# simple-loop-active1.net
KiCad netlist of a schematic drawn in EAGLE
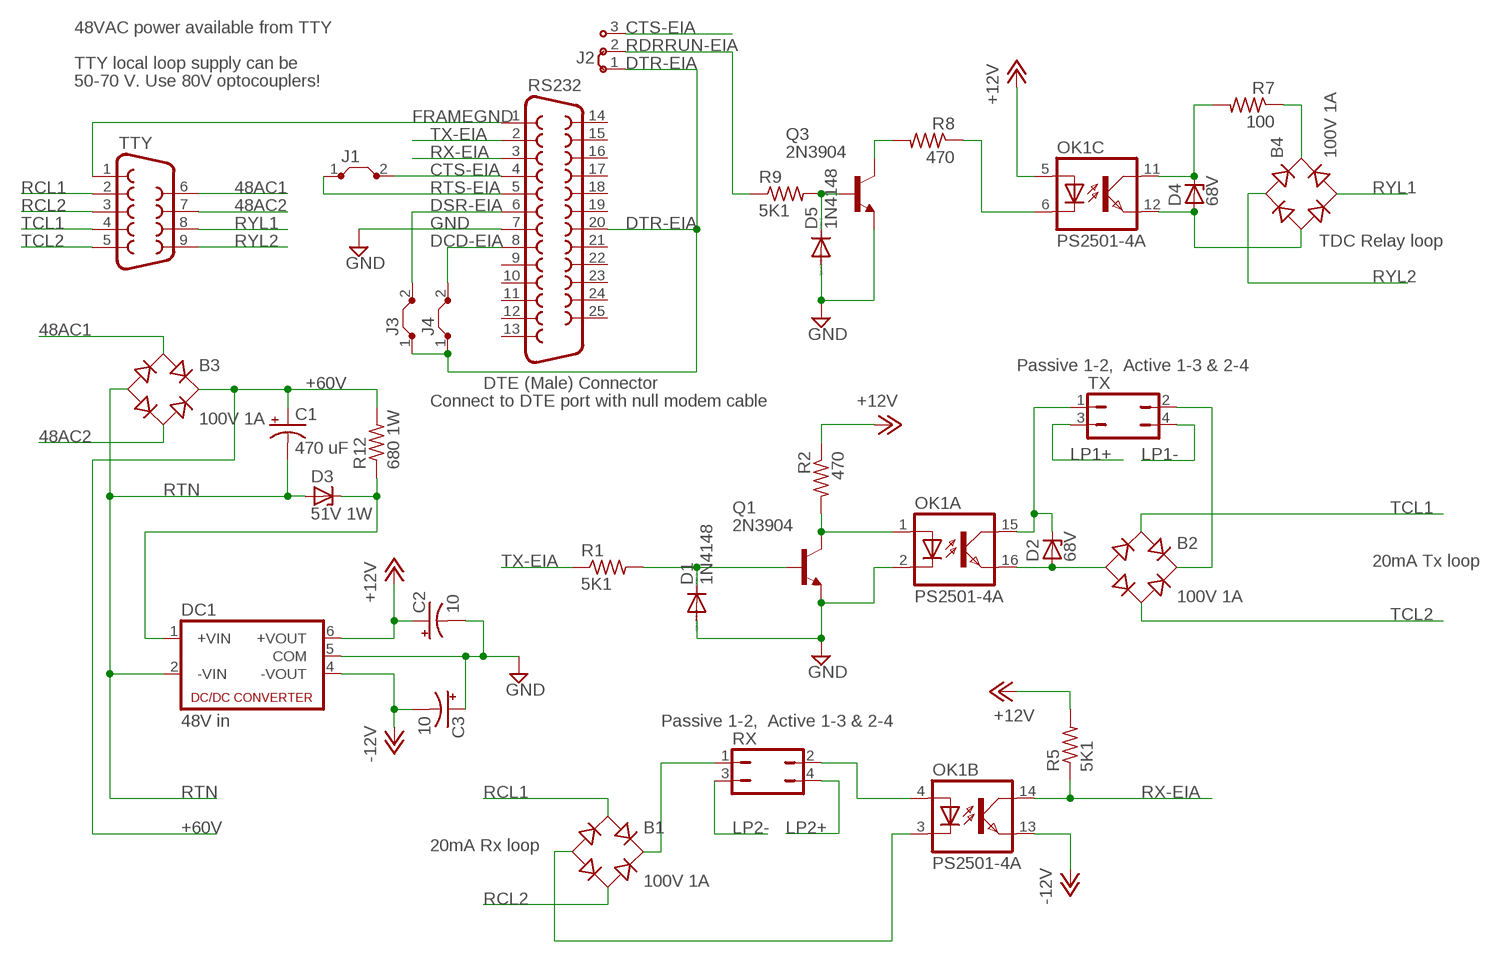
[diagram p0: schematic, sheet 1]
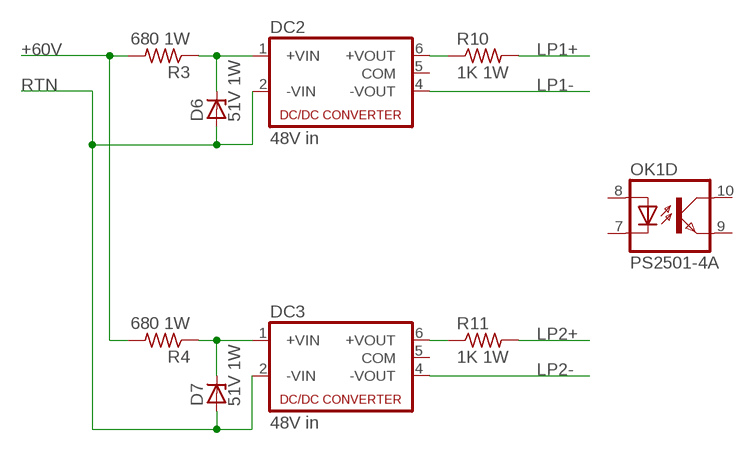
[diagram p1: schematic, sheet 2]

(export (version "E")
  (design (tool "Eeschema 10.0.6"))
  (components
    (comp (ref "B1")
      (value "100V 1A")
      (footprint "eagle-import:RB1A")
      (libsource (lib "eagle-import") (part "RB1A"))
    )
    (comp (ref "B2")
      (value "100V 1A")
      (footprint "eagle-import:RB1A")
      (libsource (lib "eagle-import") (part "RB1A"))
    )
    (comp (ref "B3")
      (value "100V 1A")
      (footprint "eagle-import:RB1A")
      (libsource (lib "eagle-import") (part "RB1A"))
    )
    (comp (ref "B4")
      (value "100V 1A")
      (footprint "eagle-import:RB1A")
      (libsource (lib "eagle-import") (part "RB1A"))
    )
    (comp (ref "C1")
      (value "470 uF")
      (footprint "eagle-import:E7,5-18")
      (libsource (lib "eagle-import") (part "CPOL-USE7.5-18"))
    )
    (comp (ref "C2")
      (value "10")
      (footprint "eagle-import:B45181A")
      (libsource (lib "eagle-import") (part "CPOL-USB45181A"))
    )
    (comp (ref "C3")
      (value "10")
      (footprint "eagle-import:B45181A")
      (libsource (lib "eagle-import") (part "CPOL-USB45181A"))
    )
    (comp (ref "D1")
      (value "1N4148")
      (footprint "eagle-import:DO35-10")
      (libsource (lib "eagle-import") (part "1N4148DO35-10"))
    )
    (comp (ref "D2")
      (value "68V")
      (footprint "eagle-import:DO41Z10")
      (libsource (lib "eagle-import") (part "ZENER-DIODEDO41Z10"))
    )
    (comp (ref "D3")
      (value "51V 1W")
      (footprint "eagle-import:DO41Z10")
      (libsource (lib "eagle-import") (part "ZENER-DIODEDO41Z10"))
    )
    (comp (ref "D4")
      (value "68V")
      (footprint "eagle-import:DO41Z10")
      (libsource (lib "eagle-import") (part "ZENER-DIODEDO41Z10"))
    )
    (comp (ref "D5")
      (value "1N4148")
      (footprint "eagle-import:DO35-10")
      (libsource (lib "eagle-import") (part "1N4148DO35-10"))
    )
    (comp (ref "DC1")
      (value "48V in")
      (footprint "eagle-import:NMA")
      (fields (field (name "MF") "C & D TECHNOLOGIES, INC") (field (name "MPN") "NMA0515SC"))
      (libsource (lib "eagle-import") (part "NMA"))
    )
    (comp (ref "J1")
      (value "J5MM")
      (footprint "eagle-import:05")
      (libsource (lib "eagle-import") (part "J5MM"))
    )
    (comp (ref "J2")
      (value "J2X5MM")
      (footprint "eagle-import:05C")
      (libsource (lib "eagle-import") (part "J2X5MM"))
    )
    (comp (ref "J3")
      (value "J5MM")
      (footprint "eagle-import:05")
      (libsource (lib "eagle-import") (part "J5MM"))
    )
    (comp (ref "J4")
      (value "J5MM")
      (footprint "eagle-import:05")
      (libsource (lib "eagle-import") (part "J5MM"))
    )
    (comp (ref "OK1")
      (value "PS2501-4A")
      (footprint "eagle-import:DIL16")
      (fields (field (name "MF") "VISHAY/TELEFUNKEN") (field (name "MPN") "ILQ1"))
      (libsource (lib "eagle-import") (part "ILQ1"))
    )
    (comp (ref "Q1")
      (value "2N3904")
      (footprint "eagle-import:TO92")
      (libsource (lib "eagle-import") (part "2N3904"))
    )
    (comp (ref "Q3")
      (value "2N3904")
      (footprint "eagle-import:TO92")
      (libsource (lib "eagle-import") (part "2N3904"))
    )
    (comp (ref "R1")
      (value "5K1")
      (footprint "eagle-import:0207_10")
      (libsource (lib "eagle-import") (part "R-US_0207/10"))
    )
    (comp (ref "R2")
      (value "470")
      (footprint "eagle-import:0207_10")
      (libsource (lib "eagle-import") (part "R-US_0207/10"))
    )
    (comp (ref "R5")
      (value "5K1")
      (footprint "eagle-import:0207_10")
      (libsource (lib "eagle-import") (part "R-US_0207/10"))
    )
    (comp (ref "R7")
      (value "100")
      (footprint "eagle-import:0207_10")
      (libsource (lib "eagle-import") (part "R-US_0207/10"))
    )
    (comp (ref "R8")
      (value "470")
      (footprint "eagle-import:0207_10")
      (libsource (lib "eagle-import") (part "R-US_0207/10"))
    )
    (comp (ref "R9")
      (value "5K1")
      (footprint "eagle-import:0207_10")
      (libsource (lib "eagle-import") (part "R-US_0207/10"))
    )
    (comp (ref "R12")
      (value "680 1W")
      (footprint "eagle-import:P0817V")
      (libsource (lib "eagle-import") (part "R-US_0817/7V"))
    )
    (comp (ref "RS232")
      (value "F25H")
      (footprint "eagle-import:F25H")
      (libsource (lib "eagle-import") (part "F25H"))
    )
    (comp (ref "RX")
      (value "JP2Q")
      (footprint "eagle-import:JP2Q")
      (libsource (lib "eagle-import") (part "JP2Q"))
    )
    (comp (ref "TTY")
      (value "F09H")
      (footprint "eagle-import:F09H")
      (libsource (lib "eagle-import") (part "F09H"))
    )
    (comp (ref "TX")
      (value "JP2Q")
      (footprint "eagle-import:JP2Q")
      (libsource (lib "eagle-import") (part "JP2Q"))
    )
    (comp (ref "D6")
      (value "51V 1W")
      (footprint "eagle-import:DO41Z10")
      (libsource (lib "eagle-import") (part "ZENER-DIODEDO41Z10"))
    )
    (comp (ref "D7")
      (value "51V 1W")
      (footprint "eagle-import:DO41Z10")
      (libsource (lib "eagle-import") (part "ZENER-DIODEDO41Z10"))
    )
    (comp (ref "DC2")
      (value "48V in")
      (footprint "eagle-import:NMA")
      (fields (field (name "MF") "C & D TECHNOLOGIES, INC") (field (name "MPN") "NMA0515SC"))
      (libsource (lib "eagle-import") (part "NMA"))
    )
    (comp (ref "DC3")
      (value "48V in")
      (footprint "eagle-import:NMA")
      (fields (field (name "MF") "C & D TECHNOLOGIES, INC") (field (name "MPN") "NMA0515SC"))
      (libsource (lib "eagle-import") (part "NMA"))
    )
    (comp (ref "R3")
      (value "680 1W")
      (footprint "eagle-import:P0817V")
      (libsource (lib "eagle-import") (part "R-US_0817/7V"))
    )
    (comp (ref "R4")
      (value "680 1W")
      (footprint "eagle-import:P0817V")
      (libsource (lib "eagle-import") (part "R-US_0817/7V"))
    )
    (comp (ref "R10")
      (value "1K 1W")
      (footprint "eagle-import:P0817V")
      (libsource (lib "eagle-import") (part "R-US_0817/7V"))
    )
    (comp (ref "R11")
      (value "1K 1W")
      (footprint "eagle-import:P0817V")
      (libsource (lib "eagle-import") (part "R-US_0817/7V"))
    )
  )
  (nets
    (net (code "1") (name "+12V") (class "Default")
      (node (ref "C2") (pin "+") (pinfunction "+_+") (pintype "passive"))
      (node (ref "DC1") (pin "6") (pinfunction "+VOUT_6") (pintype "passive"))
      (node (ref "OK1") (pin "5") (pinfunction "A_5") (pintype "passive"))
      (node (ref "R2") (pin "1") (pinfunction "1_1") (pintype "passive"))
      (node (ref "R5") (pin "2") (pinfunction "2_2") (pintype "passive"))
    )
    (net (code "2") (name "+60V") (class "Default")
      (node (ref "B3") (pin "+") (pinfunction "+_+") (pintype "passive"))
      (node (ref "C1") (pin "+") (pinfunction "+_+") (pintype "passive"))
      (node (ref "R12") (pin "2") (pinfunction "2_2") (pintype "passive"))
      (node (ref "R3") (pin "2") (pinfunction "2_2") (pintype "passive"))
      (node (ref "R4") (pin "2") (pinfunction "2_2") (pintype "passive"))
    )
    (net (code "3") (name "-12V") (class "Default")
      (node (ref "C3") (pin "-") (pinfunction "-_-") (pintype "passive"))
      (node (ref "DC1") (pin "4") (pinfunction "-VOUT_4") (pintype "passive"))
      (node (ref "OK1") (pin "13") (pinfunction "EMIT_13") (pintype "passive"))
    )
    (net (code "4") (name "48AC1") (class "Default")
      (node (ref "B3") (pin "AC1") (pinfunction "AC1_AC1") (pintype "passive"))
      (node (ref "TTY") (pin "6") (pinfunction "6_6") (pintype "passive"))
    )
    (net (code "5") (name "48AC2") (class "Default")
      (node (ref "B3") (pin "AC2") (pinfunction "AC2_AC2") (pintype "passive"))
      (node (ref "TTY") (pin "7") (pinfunction "7_7") (pintype "passive"))
    )
    (net (code "6") (name "CTS-EIA") (class "Default")
      (node (ref "J1") (pin "2") (pinfunction "2_2") (pintype "passive"))
      (node (ref "J2") (pin "3") (pinfunction "3_3") (pintype "passive"))
      (node (ref "RS232") (pin "4") (pinfunction "4_4") (pintype "passive"))
    )
    (net (code "7") (name "DCD-EIA") (class "Default")
      (node (ref "J4") (pin "2") (pinfunction "2_2") (pintype "passive"))
      (node (ref "RS232") (pin "8") (pinfunction "8_8") (pintype "passive"))
    )
    (net (code "8") (name "DSR-EIA") (class "Default")
      (node (ref "J3") (pin "2") (pinfunction "2_2") (pintype "passive"))
      (node (ref "RS232") (pin "6") (pinfunction "6_6") (pintype "passive"))
    )
    (net (code "9") (name "DTR-EIA") (class "Default")
      (node (ref "J2") (pin "1") (pinfunction "1_1") (pintype "passive"))
      (node (ref "J3") (pin "1") (pinfunction "1_1") (pintype "passive"))
      (node (ref "J4") (pin "1") (pinfunction "1_1") (pintype "passive"))
      (node (ref "RS232") (pin "20") (pinfunction "20_20") (pintype "passive"))
    )
    (net (code "10") (name "FRAMEGND") (class "Default")
      (node (ref "RS232") (pin "1") (pinfunction "1_1") (pintype "passive"))
      (node (ref "TTY") (pin "1") (pinfunction "1_1") (pintype "passive"))
    )
    (net (code "11") (name "GND") (class "Default")
      (node (ref "C2") (pin "-") (pinfunction "-_-") (pintype "passive"))
      (node (ref "C3") (pin "+") (pinfunction "+_+") (pintype "passive"))
      (node (ref "D1") (pin "A") (pinfunction "A_A") (pintype "passive"))
      (node (ref "D5") (pin "A") (pinfunction "A_A") (pintype "passive"))
      (node (ref "DC1") (pin "5") (pinfunction "COM_5") (pintype "passive"))
      (node (ref "OK1") (pin "2") (pinfunction "C_2") (pintype "passive"))
      (node (ref "Q1") (pin "3") (pinfunction "E_3") (pintype "passive"))
      (node (ref "Q3") (pin "3") (pinfunction "E_3") (pintype "passive"))
      (node (ref "RS232") (pin "7") (pinfunction "7_7") (pintype "passive"))
    )
    (net (code "12") (name "LP1+") (class "Default")
      (node (ref "R10") (pin "2") (pinfunction "2_2") (pintype "passive"))
      (node (ref "TX") (pin "3") (pinfunction "3_3") (pintype "passive"))
    )
    (net (code "13") (name "LP1-") (class "Default")
      (node (ref "DC2") (pin "4") (pinfunction "-VOUT_4") (pintype "passive"))
      (node (ref "TX") (pin "4") (pinfunction "4_4") (pintype "passive"))
    )
    (net (code "14") (name "LP2+") (class "Default")
      (node (ref "R11") (pin "2") (pinfunction "2_2") (pintype "passive"))
      (node (ref "RX") (pin "4") (pinfunction "4_4") (pintype "passive"))
    )
    (net (code "15") (name "LP2-") (class "Default")
      (node (ref "DC3") (pin "4") (pinfunction "-VOUT_4") (pintype "passive"))
      (node (ref "RX") (pin "3") (pinfunction "3_3") (pintype "passive"))
    )
    (net (code "16") (name "Net-(B1-Pad+)") (class "Default")
      (node (ref "B1") (pin "+") (pinfunction "+_+") (pintype "passive"))
      (node (ref "RX") (pin "1") (pinfunction "1_1") (pintype "passive"))
    )
    (net (code "17") (name "Net-(B2-Pad+)") (class "Default")
      (node (ref "B2") (pin "+") (pinfunction "+_+") (pintype "passive"))
      (node (ref "TX") (pin "2") (pinfunction "2_2") (pintype "passive"))
    )
    (net (code "18") (name "Net-(B4-Pad+)") (class "Default")
      (node (ref "B4") (pin "+") (pinfunction "+_+") (pintype "passive"))
      (node (ref "R7") (pin "1") (pinfunction "1_1") (pintype "passive"))
    )
    (net (code "19") (name "Net-(DC1-+VIN)") (class "Default")
      (node (ref "D3") (pin "C") (pinfunction "C_C") (pintype "passive"))
      (node (ref "DC1") (pin "1") (pinfunction "+VIN_1") (pintype "passive"))
      (node (ref "R12") (pin "1") (pinfunction "1_1") (pintype "passive"))
    )
    (net (code "20") (name "Net-(DC2-+VIN)") (class "Default")
      (node (ref "D6") (pin "C") (pinfunction "C_C") (pintype "passive"))
      (node (ref "DC2") (pin "1") (pinfunction "+VIN_1") (pintype "passive"))
      (node (ref "R3") (pin "1") (pinfunction "1_1") (pintype "passive"))
    )
    (net (code "21") (name "Net-(DC2-+VOUT)") (class "Default")
      (node (ref "DC2") (pin "6") (pinfunction "+VOUT_6") (pintype "passive"))
      (node (ref "R10") (pin "1") (pinfunction "1_1") (pintype "passive"))
    )
    (net (code "22") (name "Net-(DC3-+VIN)") (class "Default")
      (node (ref "D7") (pin "C") (pinfunction "C_C") (pintype "passive"))
      (node (ref "DC3") (pin "1") (pinfunction "+VIN_1") (pintype "passive"))
      (node (ref "R4") (pin "1") (pinfunction "1_1") (pintype "passive"))
    )
    (net (code "23") (name "Net-(DC3-+VOUT)") (class "Default")
      (node (ref "DC3") (pin "6") (pinfunction "+VOUT_6") (pintype "passive"))
      (node (ref "R11") (pin "1") (pinfunction "1_1") (pintype "passive"))
    )
    (net (code "24") (name "Net-(OK1A-A)") (class "Default")
      (node (ref "OK1") (pin "1") (pinfunction "A_1") (pintype "passive"))
      (node (ref "Q1") (pin "1") (pinfunction "C_1") (pintype "passive"))
      (node (ref "R2") (pin "2") (pinfunction "2_2") (pintype "passive"))
    )
    (net (code "25") (name "Net-(OK1A-COL)") (class "Default")
      (node (ref "D2") (pin "C") (pinfunction "C_C") (pintype "passive"))
      (node (ref "OK1") (pin "15") (pinfunction "COL_15") (pintype "passive"))
      (node (ref "TX") (pin "1") (pinfunction "1_1") (pintype "passive"))
    )
    (net (code "26") (name "Net-(OK1A-EMIT)") (class "Default")
      (node (ref "B2") (pin "-") (pinfunction "-_-") (pintype "passive"))
      (node (ref "D2") (pin "A") (pinfunction "A_A") (pintype "passive"))
      (node (ref "OK1") (pin "16") (pinfunction "EMIT_16") (pintype "passive"))
    )
    (net (code "27") (name "Net-(OK1B-A)") (class "Default")
      (node (ref "OK1") (pin "4") (pinfunction "A_4") (pintype "passive"))
      (node (ref "RX") (pin "2") (pinfunction "2_2") (pintype "passive"))
    )
    (net (code "28") (name "Net-(OK1B-C)") (class "Default")
      (node (ref "B1") (pin "-") (pinfunction "-_-") (pintype "passive"))
      (node (ref "OK1") (pin "3") (pinfunction "C_3") (pintype "passive"))
    )
    (net (code "29") (name "Net-(OK1C-C)") (class "Default")
      (node (ref "OK1") (pin "6") (pinfunction "C_6") (pintype "passive"))
      (node (ref "R8") (pin "1") (pinfunction "1_1") (pintype "passive"))
    )
    (net (code "30") (name "Net-(OK1C-COL)") (class "Default")
      (node (ref "D4") (pin "C") (pinfunction "C_C") (pintype "passive"))
      (node (ref "OK1") (pin "11") (pinfunction "COL_11") (pintype "passive"))
      (node (ref "R7") (pin "2") (pinfunction "2_2") (pintype "passive"))
    )
    (net (code "31") (name "Net-(OK1C-EMIT)") (class "Default")
      (node (ref "B4") (pin "-") (pinfunction "-_-") (pintype "passive"))
      (node (ref "D4") (pin "A") (pinfunction "A_A") (pintype "passive"))
      (node (ref "OK1") (pin "12") (pinfunction "EMIT_12") (pintype "passive"))
    )
    (net (code "32") (name "Net-(Q1-B)") (class "Default")
      (node (ref "D1") (pin "C") (pinfunction "C_C") (pintype "passive"))
      (node (ref "Q1") (pin "2") (pinfunction "B_2") (pintype "passive"))
      (node (ref "R1") (pin "2") (pinfunction "2_2") (pintype "passive"))
    )
    (net (code "33") (name "Net-(Q3-B)") (class "Default")
      (node (ref "D5") (pin "C") (pinfunction "C_C") (pintype "passive"))
      (node (ref "Q3") (pin "2") (pinfunction "B_2") (pintype "passive"))
      (node (ref "R9") (pin "2") (pinfunction "2_2") (pintype "passive"))
    )
    (net (code "34") (name "Net-(Q3-C)") (class "Default")
      (node (ref "Q3") (pin "1") (pinfunction "C_1") (pintype "passive"))
      (node (ref "R8") (pin "2") (pinfunction "2_2") (pintype "passive"))
    )
    (net (code "35") (name "RCL1") (class "Default")
      (node (ref "B1") (pin "AC1") (pinfunction "AC1_AC1") (pintype "passive"))
      (node (ref "TTY") (pin "2") (pinfunction "2_2") (pintype "passive"))
    )
    (net (code "36") (name "RCL2") (class "Default")
      (node (ref "B1") (pin "AC2") (pinfunction "AC2_AC2") (pintype "passive"))
      (node (ref "TTY") (pin "3") (pinfunction "3_3") (pintype "passive"))
    )
    (net (code "37") (name "RDRRUN-EIA") (class "Default")
      (node (ref "J2") (pin "2") (pinfunction "2_2") (pintype "passive"))
      (node (ref "R9") (pin "1") (pinfunction "1_1") (pintype "passive"))
    )
    (net (code "38") (name "RTN") (class "Default")
      (node (ref "B3") (pin "-") (pinfunction "-_-") (pintype "passive"))
      (node (ref "C1") (pin "-") (pinfunction "-_-") (pintype "passive"))
      (node (ref "D3") (pin "A") (pinfunction "A_A") (pintype "passive"))
      (node (ref "D6") (pin "A") (pinfunction "A_A") (pintype "passive"))
      (node (ref "D7") (pin "A") (pinfunction "A_A") (pintype "passive"))
      (node (ref "DC1") (pin "2") (pinfunction "-VIN_2") (pintype "passive"))
      (node (ref "DC2") (pin "2") (pinfunction "-VIN_2") (pintype "passive"))
      (node (ref "DC3") (pin "2") (pinfunction "-VIN_2") (pintype "passive"))
    )
    (net (code "39") (name "RTS-EIA") (class "Default")
      (node (ref "J1") (pin "1") (pinfunction "1_1") (pintype "passive"))
      (node (ref "RS232") (pin "5") (pinfunction "5_5") (pintype "passive"))
    )
    (net (code "40") (name "RX-EIA") (class "Default")
      (node (ref "OK1") (pin "14") (pinfunction "COL_14") (pintype "passive"))
      (node (ref "R5") (pin "1") (pinfunction "1_1") (pintype "passive"))
      (node (ref "RS232") (pin "3") (pinfunction "3_3") (pintype "passive"))
    )
    (net (code "41") (name "RYL1") (class "Default")
      (node (ref "B4") (pin "AC2") (pinfunction "AC2_AC2") (pintype "passive"))
      (node (ref "TTY") (pin "8") (pinfunction "8_8") (pintype "passive"))
    )
    (net (code "42") (name "RYL2") (class "Default")
      (node (ref "B4") (pin "AC1") (pinfunction "AC1_AC1") (pintype "passive"))
      (node (ref "TTY") (pin "9") (pinfunction "9_9") (pintype "passive"))
    )
    (net (code "43") (name "TCL1") (class "Default")
      (node (ref "B2") (pin "AC1") (pinfunction "AC1_AC1") (pintype "passive"))
      (node (ref "TTY") (pin "4") (pinfunction "4_4") (pintype "passive"))
    )
    (net (code "44") (name "TCL2") (class "Default")
      (node (ref "B2") (pin "AC2") (pinfunction "AC2_AC2") (pintype "passive"))
      (node (ref "TTY") (pin "5") (pinfunction "5_5") (pintype "passive"))
    )
    (net (code "45") (name "TX-EIA") (class "Default")
      (node (ref "R1") (pin "1") (pinfunction "1_1") (pintype "passive"))
      (node (ref "RS232") (pin "2") (pinfunction "2_2") (pintype "passive"))
    )
    (net (code "46") (name "unconnected-(DC2-COM-Pad5)") (class "Default")
      (node (ref "DC2") (pin "5") (pinfunction "COM_5") (pintype "passive"))
    )
    (net (code "47") (name "unconnected-(DC3-COM-Pad5)") (class "Default")
      (node (ref "DC3") (pin "5") (pinfunction "COM_5") (pintype "passive"))
    )
    (net (code "48") (name "unconnected-(OK1D-A-Pad8)") (class "Default")
      (node (ref "OK1") (pin "8") (pinfunction "A_8") (pintype "passive"))
    )
    (net (code "49") (name "unconnected-(OK1D-C-Pad7)") (class "Default")
      (node (ref "OK1") (pin "7") (pinfunction "C_7") (pintype "passive"))
    )
    (net (code "50") (name "unconnected-(OK1D-COL-Pad10)") (class "Default")
      (node (ref "OK1") (pin "10") (pinfunction "COL_10") (pintype "passive"))
    )
    (net (code "51") (name "unconnected-(OK1D-EMIT-Pad9)") (class "Default")
      (node (ref "OK1") (pin "9") (pinfunction "EMIT_9") (pintype "passive"))
    )
    (net (code "52") (name "unconnected-(RS232-Pad9)") (class "Default")
      (node (ref "RS232") (pin "9") (pinfunction "9_9") (pintype "passive"))
    )
    (net (code "53") (name "unconnected-(RS232-Pad10)") (class "Default")
      (node (ref "RS232") (pin "10") (pinfunction "10_10") (pintype "passive"))
    )
    (net (code "54") (name "unconnected-(RS232-Pad11)") (class "Default")
      (node (ref "RS232") (pin "11") (pinfunction "11_11") (pintype "passive"))
    )
    (net (code "55") (name "unconnected-(RS232-Pad12)") (class "Default")
      (node (ref "RS232") (pin "12") (pinfunction "12_12") (pintype "passive"))
    )
    (net (code "56") (name "unconnected-(RS232-Pad13)") (class "Default")
      (node (ref "RS232") (pin "13") (pinfunction "13_13") (pintype "passive"))
    )
    (net (code "57") (name "unconnected-(RS232-Pad14)") (class "Default")
      (node (ref "RS232") (pin "14") (pinfunction "14_14") (pintype "passive"))
    )
    (net (code "58") (name "unconnected-(RS232-Pad15)") (class "Default")
      (node (ref "RS232") (pin "15") (pinfunction "15_15") (pintype "passive"))
    )
    (net (code "59") (name "unconnected-(RS232-Pad16)") (class "Default")
      (node (ref "RS232") (pin "16") (pinfunction "16_16") (pintype "passive"))
    )
    (net (code "60") (name "unconnected-(RS232-Pad17)") (class "Default")
      (node (ref "RS232") (pin "17") (pinfunction "17_17") (pintype "passive"))
    )
    (net (code "61") (name "unconnected-(RS232-Pad18)") (class "Default")
      (node (ref "RS232") (pin "18") (pinfunction "18_18") (pintype "passive"))
    )
    (net (code "62") (name "unconnected-(RS232-Pad19)") (class "Default")
      (node (ref "RS232") (pin "19") (pinfunction "19_19") (pintype "passive"))
    )
    (net (code "63") (name "unconnected-(RS232-Pad21)") (class "Default")
      (node (ref "RS232") (pin "21") (pinfunction "21_21") (pintype "passive"))
    )
    (net (code "64") (name "unconnected-(RS232-Pad22)") (class "Default")
      (node (ref "RS232") (pin "22") (pinfunction "22_22") (pintype "passive"))
    )
    (net (code "65") (name "unconnected-(RS232-Pad23)") (class "Default")
      (node (ref "RS232") (pin "23") (pinfunction "23_23") (pintype "passive"))
    )
    (net (code "66") (name "unconnected-(RS232-Pad24)") (class "Default")
      (node (ref "RS232") (pin "24") (pinfunction "24_24") (pintype "passive"))
    )
    (net (code "67") (name "unconnected-(RS232-Pad25)") (class "Default")
      (node (ref "RS232") (pin "25") (pinfunction "25_25") (pintype "passive"))
    )
  )
)
